# z-two.net
KiCad netlist of a schematic drawn in EAGLE
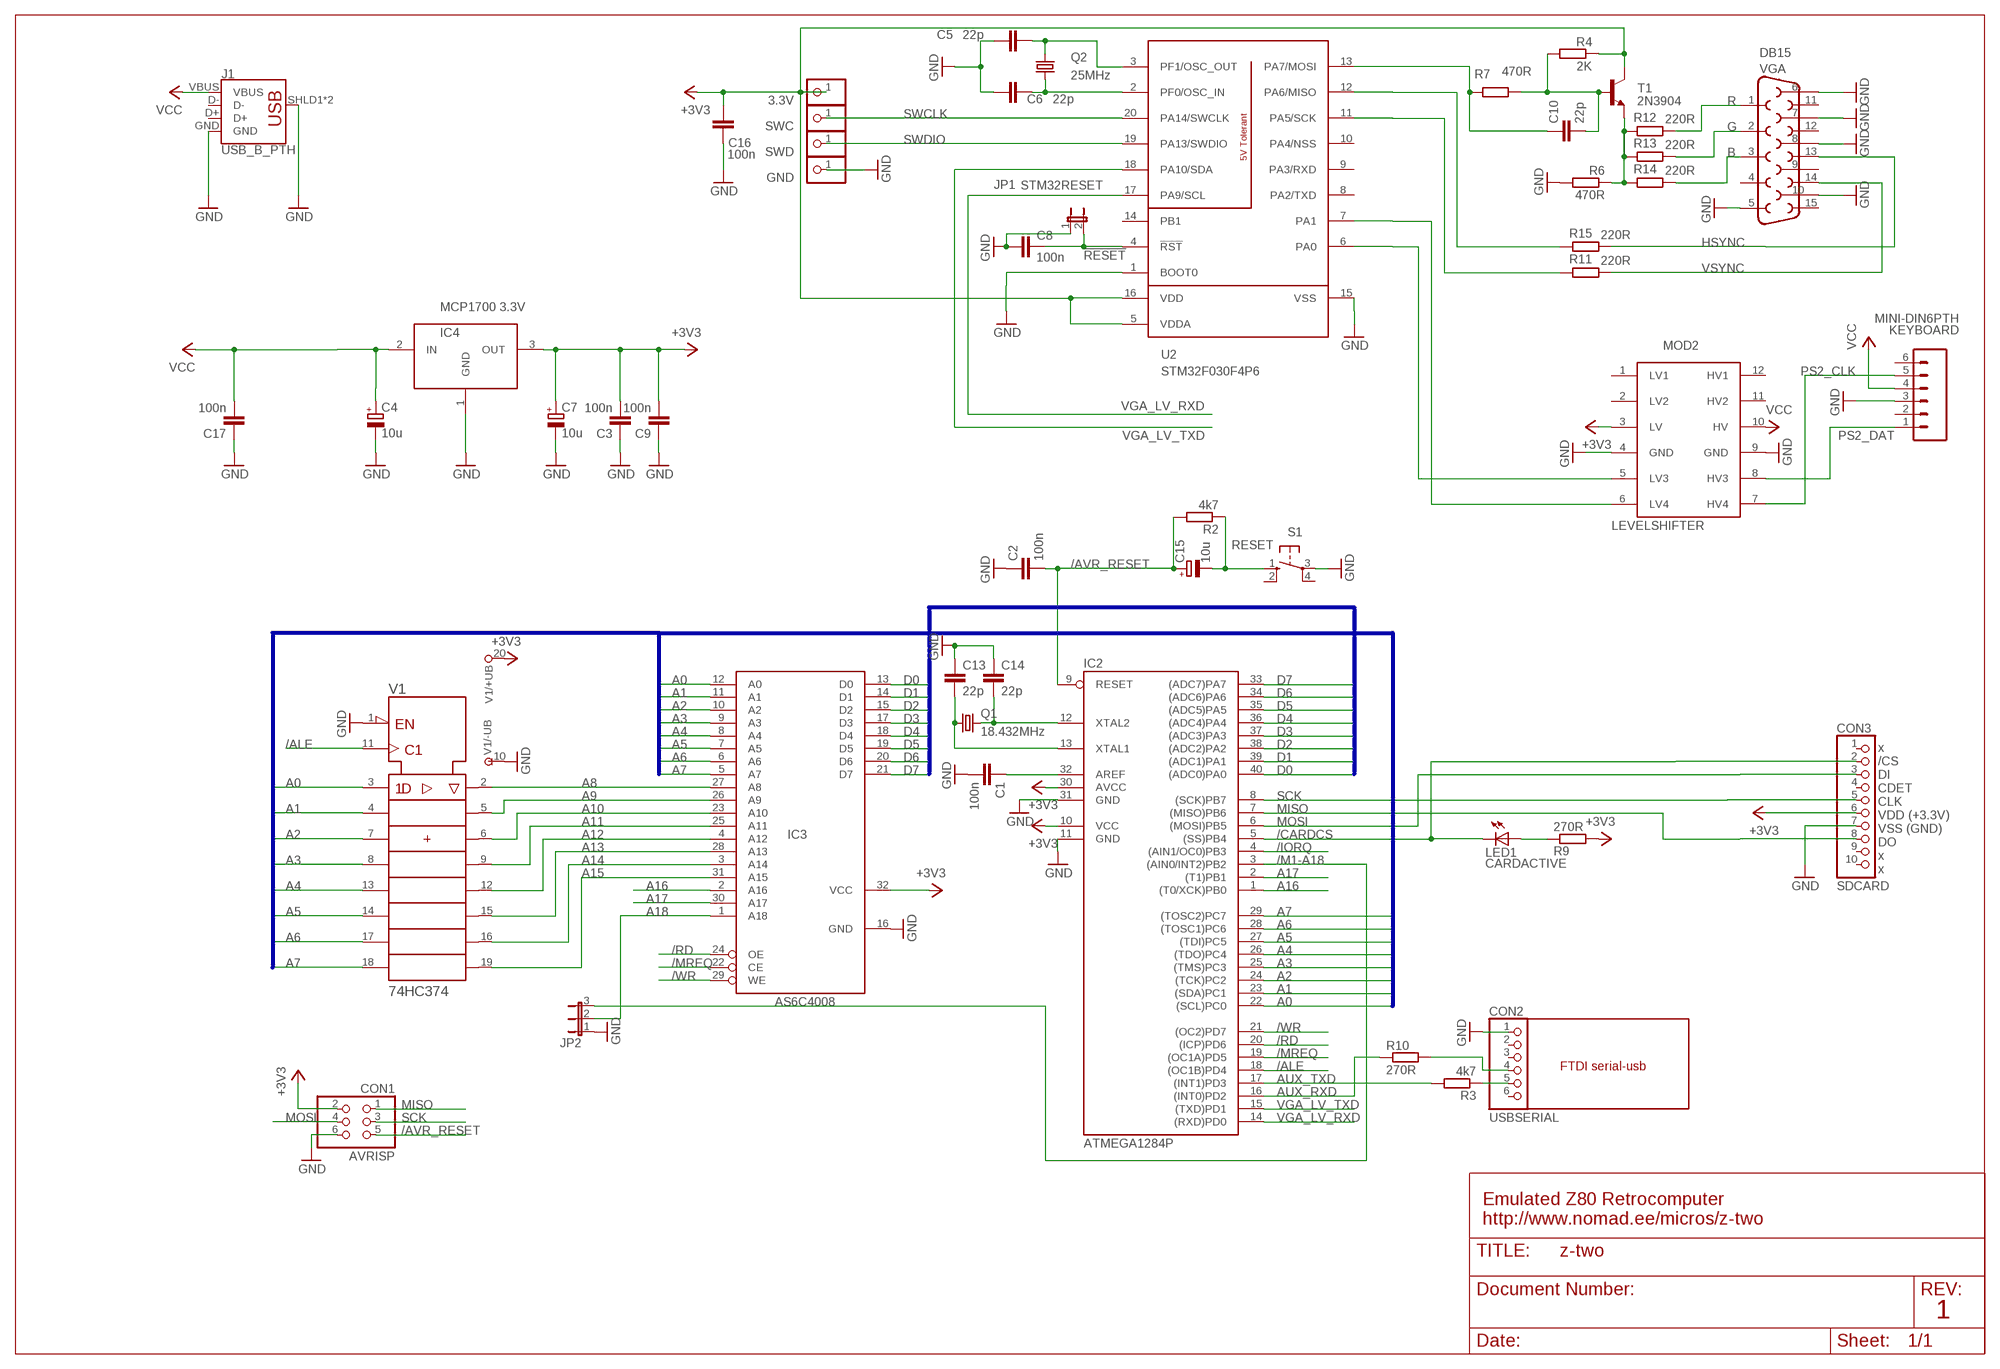
[diagram p0: schematic, sheet 1]

(export (version "E")
  (design (tool "Eeschema 10.0.6"))
  (components
    (comp (ref "3.3V")
      (value "PINHD-1X1")
      (footprint "eagle-import:1X01")
      (libsource (lib "eagle-import") (part "PINHD-1X1"))
    )
    (comp (ref "C1")
      (value "100n")
      (footprint "eagle-import:C025-025X050")
      (fields (field (name "PARTNO") "0.1UF, 0603"))
      (libsource (lib "eagle-import") (part "C-EU025-025X050"))
    )
    (comp (ref "C2")
      (value "100n")
      (footprint "eagle-import:C025-025X050")
      (fields (field (name "PARTNO") "0.1UF, 0603"))
      (libsource (lib "eagle-import") (part "C-EU025-025X050"))
    )
    (comp (ref "C3")
      (value "100n")
      (footprint "eagle-import:C025-025X050")
      (fields (field (name "PARTNO") "0.1UF, 0603"))
      (libsource (lib "eagle-import") (part "C-EU025-025X050"))
    )
    (comp (ref "C4")
      (value "10u")
      (footprint "eagle-import:E2,5-5")
      (libsource (lib "eagle-import") (part "CPOL-EUE2.5-5"))
    )
    (comp (ref "C5")
      (value "22p")
      (footprint "eagle-import:C025-025X050")
      (fields (field (name "PARTNO") "22PF, 0603"))
      (libsource (lib "eagle-import") (part "C-EU025-025X050"))
    )
    (comp (ref "C6")
      (value "22p")
      (footprint "eagle-import:C025-025X050")
      (fields (field (name "PARTNO") "22PF, 0603"))
      (libsource (lib "eagle-import") (part "C-EU025-025X050"))
    )
    (comp (ref "C7")
      (value "10u")
      (footprint "eagle-import:E2,5-5")
      (libsource (lib "eagle-import") (part "CPOL-EUE2.5-5"))
    )
    (comp (ref "C8")
      (value "100n")
      (footprint "eagle-import:C025-025X050")
      (fields (field (name "PARTNO") "0.1UF, 0603"))
      (libsource (lib "eagle-import") (part "C-EU025-025X050"))
    )
    (comp (ref "C9")
      (value "100n")
      (footprint "eagle-import:C025-025X050")
      (fields (field (name "PARTNO") "0.1UF, 0603"))
      (libsource (lib "eagle-import") (part "C-EU025-025X050"))
    )
    (comp (ref "C10")
      (value "22p")
      (footprint "eagle-import:C025-025X050")
      (fields (field (name "PARTNO") "22PF, 0603"))
      (libsource (lib "eagle-import") (part "C-EU025-025X050"))
    )
    (comp (ref "C13")
      (value "22p")
      (footprint "eagle-import:C025-025X050")
      (fields (field (name "PARTNO") "0.1UF, 0603"))
      (libsource (lib "eagle-import") (part "C-EU025-025X050"))
    )
    (comp (ref "C14")
      (value "22p")
      (footprint "eagle-import:C025-025X050")
      (fields (field (name "PARTNO") "0.1UF, 0603"))
      (libsource (lib "eagle-import") (part "C-EU025-025X050"))
    )
    (comp (ref "C15")
      (value "10u")
      (footprint "eagle-import:E2,5-5")
      (libsource (lib "eagle-import") (part "CPOL-EUE2.5-5"))
    )
    (comp (ref "C16")
      (value "100n")
      (footprint "eagle-import:C025-025X050")
      (fields (field (name "PARTNO") "0.1UF, 0603"))
      (libsource (lib "eagle-import") (part "C-EU025-025X050"))
    )
    (comp (ref "C17")
      (value "100n")
      (footprint "eagle-import:C025-025X050")
      (fields (field (name "PARTNO") "0.1UF, 0603"))
      (libsource (lib "eagle-import") (part "C-EU025-025X050"))
    )
    (comp (ref "CON1")
      (value "AVRISP")
      (footprint "eagle-import:2X03")
      (libsource (lib "eagle-import") (part "PINHD-2X3"))
    )
    (comp (ref "CON2")
      (value "USBSERIAL")
      (footprint "eagle-import:1X06")
      (libsource (lib "eagle-import") (part "PINHD-1X6"))
    )
    (comp (ref "CON3")
      (value "SDCARD")
      (footprint "eagle-import:1X10")
      (libsource (lib "eagle-import") (part "PINHD-1X10"))
    )
    (comp (ref "GND")
      (value "PINHD-1X1")
      (footprint "eagle-import:1X01")
      (libsource (lib "eagle-import") (part "PINHD-1X1"))
    )
    (comp (ref "IC2")
      (value "ATMEGA1284P")
      (footprint "eagle-import:DIL40")
      (fields (field (name "MPN") "ATMEGA32-16PU"))
      (libsource (lib "eagle-import") (part "MEGA32-P"))
    )
    (comp (ref "IC3")
      (value "AS6C4008")
      (footprint "eagle-import:DIP32")
      (libsource (lib "eagle-import") (part "AS6C4008DIP32"))
    )
    (comp (ref "IC4")
      (value "MCP1700 3.3V")
      (footprint "eagle-import:TO-92")
      (libsource (lib "eagle-import") (part "MCP1700TO92"))
    )
    (comp (ref "J1")
      (value "USB_B_PTH")
      (footprint "eagle-import:USB-B-PTH")
      (libsource (lib "eagle-import") (part "USB_B_PTH"))
    )
    (comp (ref "JP1")
      (value "STM32RESET")
      (footprint "eagle-import:1X02")
      (libsource (lib "eagle-import") (part "JUMPER-2PTH"))
    )
    (comp (ref "JP2")
      (value "JP2E")
      (footprint "eagle-import:JP2")
      (libsource (lib "eagle-import") (part "JP2E"))
    )
    (comp (ref "KEYBOARD")
      (value "MINI-DIN6PTH")
      (footprint "eagle-import:MINI-DIN6")
      (libsource (lib "eagle-import") (part "MINI-DIN6PTH"))
    )
    (comp (ref "LED1")
      (value "CARDACTIVE")
      (footprint "eagle-import:LED3MM")
      (libsource (lib "eagle-import") (part "LED3MM"))
    )
    (comp (ref "MOD2")
      (value "LEVELSHIFTER")
      (footprint "eagle-import:LAVELSHIFTER_N")
      (libsource (lib "eagle-import") (part "LEVELSHIFTERNARROW"))
    )
    (comp (ref "Q1")
      (value "18.432MHz")
      (footprint "eagle-import:HC49_S")
      (libsource (lib "eagle-import") (part "CRYSTALHC49S"))
    )
    (comp (ref "Q2")
      (value "25MHz")
      (footprint "eagle-import:HC49_S")
      (libsource (lib "eagle-import") (part "CRYSTALHC49S"))
    )
    (comp (ref "R2")
      (value "4k7")
      (footprint "eagle-import:0204_7")
      (libsource (lib "eagle-import") (part "R-EU_0204/7"))
    )
    (comp (ref "R3")
      (value "4k7")
      (footprint "eagle-import:0204_7")
      (libsource (lib "eagle-import") (part "R-EU_0204/7"))
    )
    (comp (ref "R4")
      (value "2K")
      (footprint "eagle-import:0204_7")
      (fields (field (name "PARTNO") "2K, 0603"))
      (libsource (lib "eagle-import") (part "resistor_R-EU_0204/7"))
    )
    (comp (ref "R6")
      (value "470R")
      (footprint "eagle-import:0204_7")
      (fields (field (name "PARTNO") "475R, 0603"))
      (libsource (lib "eagle-import") (part "resistor_R-EU_0204/7"))
    )
    (comp (ref "R7")
      (value "470R")
      (footprint "eagle-import:0204_7")
      (fields (field (name "PARTNO") "475R, 0603"))
      (libsource (lib "eagle-import") (part "resistor_R-EU_0204/7"))
    )
    (comp (ref "R9")
      (value "270R")
      (footprint "eagle-import:0204_7")
      (fields (field (name "PARTNO") "475R, 0603"))
      (libsource (lib "eagle-import") (part "resistor_R-EU_0204/7"))
    )
    (comp (ref "R10")
      (value "270R")
      (footprint "eagle-import:0204_7")
      (libsource (lib "eagle-import") (part "R-EU_0204/7"))
    )
    (comp (ref "R11")
      (value "220R")
      (footprint "eagle-import:0204_7")
      (libsource (lib "eagle-import") (part "resistor_R-EU_0204/7"))
    )
    (comp (ref "R12")
      (value "220R")
      (footprint "eagle-import:0204_7")
      (libsource (lib "eagle-import") (part "resistor_R-EU_0204/7"))
    )
    (comp (ref "R13")
      (value "220R")
      (footprint "eagle-import:0204_7")
      (libsource (lib "eagle-import") (part "resistor_R-EU_0204/7"))
    )
    (comp (ref "R14")
      (value "220R")
      (footprint "eagle-import:0204_7")
      (libsource (lib "eagle-import") (part "resistor_R-EU_0204/7"))
    )
    (comp (ref "R15")
      (value "220R")
      (footprint "eagle-import:0204_7")
      (libsource (lib "eagle-import") (part "resistor_R-EU_0204/7"))
    )
    (comp (ref "S1")
      (value "RESET")
      (footprint "eagle-import:B3F-10XX")
      (fields (field (name "MPN") "B3F-1000"))
      (libsource (lib "eagle-import") (part "10-XX"))
    )
    (comp (ref "SWC")
      (value "PINHD-1X1")
      (footprint "eagle-import:1X01")
      (libsource (lib "eagle-import") (part "PINHD-1X1"))
    )
    (comp (ref "SWD")
      (value "PINHD-1X1")
      (footprint "eagle-import:1X01")
      (libsource (lib "eagle-import") (part "PINHD-1X1"))
    )
    (comp (ref "T1")
      (value "2N3904")
      (footprint "eagle-import:TO92")
      (libsource (lib "eagle-import") (part "2N3904"))
    )
    (comp (ref "U2")
      (value "STM32F030F4P6")
      (footprint "eagle-import:MISC-PROCESSOR_TSSOP20")
      (libsource (lib "eagle-import") (part "MISC-PROCESSOR_STM32F030F4P6"))
    )
    (comp (ref "V1")
      (value "74HC374")
      (footprint "eagle-import:DIL20")
      (libsource (lib "eagle-import") (part "74374N"))
    )
    (comp (ref "VGA")
      (value "DB15")
      (footprint "eagle-import:DB15")
      (libsource (lib "eagle-import") (part "DB15"))
    )
  )
  (nets
    (net (code "1") (name "+3V3") (class "Default")
      (node (ref "3.3V") (pin "1") (pinfunction "1_1") (pintype "passive"))
      (node (ref "C16") (pin "1") (pinfunction "1_1") (pintype "passive"))
      (node (ref "C3") (pin "2") (pinfunction "2_2") (pintype "passive"))
      (node (ref "C7") (pin "+") (pinfunction "+_+") (pintype "passive"))
      (node (ref "C9") (pin "2") (pinfunction "2_2") (pintype "passive"))
      (node (ref "CON1") (pin "2") (pinfunction "2_2") (pintype "passive"))
      (node (ref "CON3") (pin "6") (pinfunction "6_6") (pintype "passive"))
      (node (ref "IC2") (pin "10") (pinfunction "VCC_10") (pintype "power_in"))
      (node (ref "IC2") (pin "30") (pinfunction "AVCC_30") (pintype "power_in"))
      (node (ref "IC3") (pin "32") (pinfunction "VCC_32") (pintype "power_in"))
      (node (ref "IC4") (pin "3") (pinfunction "OUT_3") (pintype "bidirectional"))
      (node (ref "MOD2") (pin "3") (pinfunction "LV_3") (pintype "bidirectional"))
      (node (ref "R4") (pin "1") (pinfunction "1_1") (pintype "passive"))
      (node (ref "R9") (pin "2") (pinfunction "2_2") (pintype "passive"))
      (node (ref "T1") (pin "1") (pinfunction "C_1") (pintype "passive"))
      (node (ref "U2") (pin "16") (pinfunction "VDD_16") (pintype "input"))
      (node (ref "U2") (pin "5") (pinfunction "VDDA_5") (pintype "input"))
      (node (ref "V1") (pin "20") (pinfunction "+UB_20") (pintype "power_in"))
    )
    (net (code "2") (name "/A0") (class "Default")
      (node (ref "IC2") (pin "22") (pinfunction "(SCL)PC0_22") (pintype "bidirectional"))
      (node (ref "IC3") (pin "12") (pinfunction "A0_12") (pintype "input"))
      (node (ref "V1") (pin "3") (pinfunction "1D_3") (pintype "input"))
    )
    (net (code "3") (name "/A1") (class "Default")
      (node (ref "IC2") (pin "23") (pinfunction "(SDA)PC1_23") (pintype "bidirectional"))
      (node (ref "IC3") (pin "11") (pinfunction "A1_11") (pintype "input"))
      (node (ref "V1") (pin "4") (pinfunction "2D_4") (pintype "input"))
    )
    (net (code "4") (name "/A2") (class "Default")
      (node (ref "IC2") (pin "24") (pinfunction "(TCK)PC2_24") (pintype "bidirectional"))
      (node (ref "IC3") (pin "10") (pinfunction "A2_10") (pintype "input"))
      (node (ref "V1") (pin "7") (pinfunction "3D_7") (pintype "input"))
    )
    (net (code "5") (name "/A3") (class "Default")
      (node (ref "IC2") (pin "25") (pinfunction "(TMS)PC3_25") (pintype "bidirectional"))
      (node (ref "IC3") (pin "9") (pinfunction "A3_9") (pintype "input"))
      (node (ref "V1") (pin "8") (pinfunction "4D_8") (pintype "input"))
    )
    (net (code "6") (name "/A4") (class "Default")
      (node (ref "IC2") (pin "26") (pinfunction "(TDO)PC4_26") (pintype "bidirectional"))
      (node (ref "IC3") (pin "8") (pinfunction "A4_8") (pintype "input"))
      (node (ref "V1") (pin "13") (pinfunction "5D_13") (pintype "input"))
    )
    (net (code "7") (name "/A5") (class "Default")
      (node (ref "IC2") (pin "27") (pinfunction "(TDI)PC5_27") (pintype "bidirectional"))
      (node (ref "IC3") (pin "7") (pinfunction "A5_7") (pintype "input"))
      (node (ref "V1") (pin "14") (pinfunction "6D_14") (pintype "input"))
    )
    (net (code "8") (name "/A6") (class "Default")
      (node (ref "IC2") (pin "28") (pinfunction "(TOSC1)PC6_28") (pintype "bidirectional"))
      (node (ref "IC3") (pin "6") (pinfunction "A6_6") (pintype "input"))
      (node (ref "V1") (pin "17") (pinfunction "7D_17") (pintype "input"))
    )
    (net (code "9") (name "/A7") (class "Default")
      (node (ref "IC2") (pin "29") (pinfunction "(TOSC2)PC7_29") (pintype "bidirectional"))
      (node (ref "IC3") (pin "5") (pinfunction "A7_5") (pintype "input"))
      (node (ref "V1") (pin "18") (pinfunction "8D_18") (pintype "input"))
    )
    (net (code "10") (name "/A8") (class "Default")
      (node (ref "IC3") (pin "27") (pinfunction "A8_27") (pintype "input"))
      (node (ref "V1") (pin "2") (pinfunction "1Q_2") (pintype "tri_state"))
    )
    (net (code "11") (name "/A9") (class "Default")
      (node (ref "IC3") (pin "26") (pinfunction "A9_26") (pintype "input"))
      (node (ref "V1") (pin "5") (pinfunction "2Q_5") (pintype "tri_state"))
    )
    (net (code "12") (name "/A10") (class "Default")
      (node (ref "IC3") (pin "23") (pinfunction "A10_23") (pintype "input"))
      (node (ref "V1") (pin "6") (pinfunction "3Q_6") (pintype "tri_state"))
    )
    (net (code "13") (name "/A11") (class "Default")
      (node (ref "IC3") (pin "25") (pinfunction "A11_25") (pintype "input"))
      (node (ref "V1") (pin "9") (pinfunction "4Q_9") (pintype "tri_state"))
    )
    (net (code "14") (name "/A12") (class "Default")
      (node (ref "IC3") (pin "4") (pinfunction "A12_4") (pintype "input"))
      (node (ref "V1") (pin "12") (pinfunction "5Q_12") (pintype "tri_state"))
    )
    (net (code "15") (name "/A13") (class "Default")
      (node (ref "IC3") (pin "28") (pinfunction "A13_28") (pintype "input"))
      (node (ref "V1") (pin "15") (pinfunction "6Q_15") (pintype "tri_state"))
    )
    (net (code "16") (name "/A14") (class "Default")
      (node (ref "IC3") (pin "3") (pinfunction "A14_3") (pintype "input"))
      (node (ref "V1") (pin "16") (pinfunction "7Q_16") (pintype "tri_state"))
    )
    (net (code "17") (name "/A15") (class "Default")
      (node (ref "IC3") (pin "31") (pinfunction "A15_31") (pintype "input"))
      (node (ref "V1") (pin "19") (pinfunction "8Q_19") (pintype "tri_state"))
    )
    (net (code "18") (name "/A16") (class "Default")
      (node (ref "IC2") (pin "1") (pinfunction "(T0/XCK)PB0_1") (pintype "bidirectional"))
      (node (ref "IC3") (pin "2") (pinfunction "A16_2") (pintype "input"))
    )
    (net (code "19") (name "/A17") (class "Default")
      (node (ref "IC2") (pin "2") (pinfunction "(T1)PB1_2") (pintype "bidirectional"))
      (node (ref "IC3") (pin "30") (pinfunction "A17_30") (pintype "input"))
    )
    (net (code "20") (name "/A18") (class "Default")
      (node (ref "IC3") (pin "1") (pinfunction "A18_1") (pintype "input"))
      (node (ref "JP2") (pin "2") (pinfunction "2_2") (pintype "passive"))
    )
    (net (code "21") (name "/AUX_RXD") (class "Default")
      (node (ref "IC2") (pin "16") (pinfunction "(INT0)PD2_16") (pintype "bidirectional"))
      (node (ref "R10") (pin "1") (pinfunction "1_1") (pintype "passive"))
    )
    (net (code "22") (name "/AUX_TXD") (class "Default")
      (node (ref "IC2") (pin "17") (pinfunction "(INT1)PD3_17") (pintype "bidirectional"))
      (node (ref "R3") (pin "2") (pinfunction "2_2") (pintype "passive"))
    )
    (net (code "23") (name "/B") (class "Default")
      (node (ref "R14") (pin "1") (pinfunction "1_1") (pintype "passive"))
      (node (ref "VGA") (pin "3") (pinfunction "3_3") (pintype "passive"))
    )
    (net (code "24") (name "/D0") (class "Default")
      (node (ref "IC2") (pin "40") (pinfunction "(ADC0)PA0_40") (pintype "bidirectional"))
      (node (ref "IC3") (pin "13") (pinfunction "D0_13") (pintype "bidirectional"))
    )
    (net (code "25") (name "/D1") (class "Default")
      (node (ref "IC2") (pin "39") (pinfunction "(ADC1)PA1_39") (pintype "bidirectional"))
      (node (ref "IC3") (pin "14") (pinfunction "D1_14") (pintype "bidirectional"))
    )
    (net (code "26") (name "/D2") (class "Default")
      (node (ref "IC2") (pin "38") (pinfunction "(ADC2)PA2_38") (pintype "bidirectional"))
      (node (ref "IC3") (pin "15") (pinfunction "D2_15") (pintype "bidirectional"))
    )
    (net (code "27") (name "/D3") (class "Default")
      (node (ref "IC2") (pin "37") (pinfunction "(ADC3)PA3_37") (pintype "bidirectional"))
      (node (ref "IC3") (pin "17") (pinfunction "D3_17") (pintype "bidirectional"))
    )
    (net (code "28") (name "/D4") (class "Default")
      (node (ref "IC2") (pin "36") (pinfunction "(ADC4)PA4_36") (pintype "bidirectional"))
      (node (ref "IC3") (pin "18") (pinfunction "D4_18") (pintype "bidirectional"))
    )
    (net (code "29") (name "/D5") (class "Default")
      (node (ref "IC2") (pin "35") (pinfunction "(ADC5)PA5_35") (pintype "bidirectional"))
      (node (ref "IC3") (pin "19") (pinfunction "D5_19") (pintype "bidirectional"))
    )
    (net (code "30") (name "/D6") (class "Default")
      (node (ref "IC2") (pin "34") (pinfunction "(ADC6)PA6_34") (pintype "bidirectional"))
      (node (ref "IC3") (pin "20") (pinfunction "D6_20") (pintype "bidirectional"))
    )
    (net (code "31") (name "/D7") (class "Default")
      (node (ref "IC2") (pin "33") (pinfunction "(ADC7)PA7_33") (pintype "bidirectional"))
      (node (ref "IC3") (pin "21") (pinfunction "D7_21") (pintype "bidirectional"))
    )
    (net (code "32") (name "/G") (class "Default")
      (node (ref "R13") (pin "1") (pinfunction "1_1") (pintype "passive"))
      (node (ref "VGA") (pin "2") (pinfunction "2_2") (pintype "passive"))
    )
    (net (code "33") (name "/HSYNC") (class "Default")
      (node (ref "R15") (pin "1") (pinfunction "1_1") (pintype "passive"))
      (node (ref "VGA") (pin "13") (pinfunction "13_13") (pintype "passive"))
    )
    (net (code "34") (name "/MISO") (class "Default")
      (node (ref "CON1") (pin "1") (pinfunction "1_1") (pintype "passive"))
      (node (ref "CON3") (pin "8") (pinfunction "8_8") (pintype "passive"))
      (node (ref "IC2") (pin "7") (pinfunction "(MISO)PB6_7") (pintype "bidirectional"))
    )
    (net (code "35") (name "/MOSI") (class "Default")
      (node (ref "CON1") (pin "4") (pinfunction "4_4") (pintype "passive"))
      (node (ref "CON3") (pin "3") (pinfunction "3_3") (pintype "passive"))
      (node (ref "IC2") (pin "6") (pinfunction "(MOSI)PB5_6") (pintype "bidirectional"))
    )
    (net (code "36") (name "/PS2_CLK") (class "Default")
      (node (ref "KEYBOARD") (pin "5") (pinfunction "5_5") (pintype "passive"))
      (node (ref "MOD2") (pin "7") (pinfunction "HV4_7") (pintype "bidirectional"))
    )
    (net (code "37") (name "/PS2_DAT") (class "Default")
      (node (ref "KEYBOARD") (pin "1") (pinfunction "1_1") (pintype "passive"))
      (node (ref "MOD2") (pin "8") (pinfunction "HV3_8") (pintype "bidirectional"))
    )
    (net (code "38") (name "/R") (class "Default")
      (node (ref "R12") (pin "1") (pinfunction "1_1") (pintype "passive"))
      (node (ref "VGA") (pin "1") (pinfunction "1_1") (pintype "passive"))
    )
    (net (code "39") (name "/SCK") (class "Default")
      (node (ref "CON1") (pin "3") (pinfunction "3_3") (pintype "passive"))
      (node (ref "CON3") (pin "5") (pinfunction "5_5") (pintype "passive"))
      (node (ref "IC2") (pin "8") (pinfunction "(SCK)PB7_8") (pintype "bidirectional"))
    )
    (net (code "40") (name "/SWCLK") (class "Default")
      (node (ref "SWC") (pin "1") (pinfunction "1_1") (pintype "passive"))
      (node (ref "U2") (pin "20") (pinfunction "PA14/SWCLK_20") (pintype "bidirectional"))
    )
    (net (code "41") (name "/SWDIO") (class "Default")
      (node (ref "SWD") (pin "1") (pinfunction "1_1") (pintype "passive"))
      (node (ref "U2") (pin "19") (pinfunction "PA13/SWDIO_19") (pintype "bidirectional"))
    )
    (net (code "42") (name "/VGA_LV_RXD") (class "Default")
      (node (ref "IC2") (pin "14") (pinfunction "(RXD)PD0_14") (pintype "bidirectional"))
      (node (ref "U2") (pin "17") (pinfunction "PA9/SCL_17") (pintype "bidirectional"))
    )
    (net (code "43") (name "/VGA_LV_TXD") (class "Default")
      (node (ref "IC2") (pin "15") (pinfunction "(TXD)PD1_15") (pintype "bidirectional"))
      (node (ref "U2") (pin "18") (pinfunction "PA10/SDA_18") (pintype "bidirectional"))
    )
    (net (code "44") (name "/VSYNC") (class "Default")
      (node (ref "R11") (pin "1") (pinfunction "1_1") (pintype "passive"))
      (node (ref "VGA") (pin "14") (pinfunction "14_14") (pintype "passive"))
    )
    (net (code "45") (name "/{slash}ALE") (class "Default")
      (node (ref "IC2") (pin "18") (pinfunction "(OC1B)PD4_18") (pintype "bidirectional"))
      (node (ref "V1") (pin "11") (pinfunction "CLK_11") (pintype "input"))
    )
    (net (code "46") (name "/{slash}AVR_RESET") (class "Default")
      (node (ref "C15") (pin "+") (pinfunction "+_+") (pintype "passive"))
      (node (ref "C2") (pin "2") (pinfunction "2_2") (pintype "passive"))
      (node (ref "CON1") (pin "5") (pinfunction "5_5") (pintype "passive"))
      (node (ref "IC2") (pin "9") (pinfunction "RESET_9") (pintype "input"))
      (node (ref "R2") (pin "2") (pinfunction "2_2") (pintype "passive"))
    )
    (net (code "47") (name "/{slash}CARDCS") (class "Default")
      (node (ref "CON3") (pin "2") (pinfunction "2_2") (pintype "passive"))
      (node (ref "IC2") (pin "5") (pinfunction "(SS)PB4_5") (pintype "bidirectional"))
      (node (ref "LED1") (pin "K") (pinfunction "C_K") (pintype "passive"))
    )
    (net (code "48") (name "/{slash}IORQ") (class "Default")
      (node (ref "IC2") (pin "4") (pinfunction "(AIN1/OC0)PB3_4") (pintype "bidirectional"))
    )
    (net (code "49") (name "/{slash}M1-A18") (class "Default")
      (node (ref "IC2") (pin "3") (pinfunction "(AIN0/INT2)PB2_3") (pintype "bidirectional"))
      (node (ref "JP2") (pin "3") (pinfunction "3_3") (pintype "passive"))
    )
    (net (code "50") (name "/{slash}MREQ") (class "Default")
      (node (ref "IC2") (pin "19") (pinfunction "(OC1A)PD5_19") (pintype "bidirectional"))
      (node (ref "IC3") (pin "22") (pinfunction "CE_22") (pintype "input"))
    )
    (net (code "51") (name "/{slash}RD") (class "Default")
      (node (ref "IC2") (pin "20") (pinfunction "(ICP)PD6_20") (pintype "bidirectional"))
      (node (ref "IC3") (pin "24") (pinfunction "OE_24") (pintype "input"))
    )
    (net (code "52") (name "/{slash}WR") (class "Default")
      (node (ref "IC2") (pin "21") (pinfunction "(OC2)PD7_21") (pintype "bidirectional"))
      (node (ref "IC3") (pin "29") (pinfunction "WE_29") (pintype "input"))
    )
    (net (code "53") (name "/~{RESET}") (class "Default")
      (node (ref "C8") (pin "1") (pinfunction "1_1") (pintype "passive"))
      (node (ref "JP1") (pin "2") (pinfunction "2_2") (pintype "passive"))
      (node (ref "U2") (pin "4") (pinfunction "~{RST}_4") (pintype "input"))
    )
    (net (code "54") (name "GND") (class "Default")
      (node (ref "C1") (pin "2") (pinfunction "2_2") (pintype "passive"))
      (node (ref "C13") (pin "1") (pinfunction "1_1") (pintype "passive"))
      (node (ref "C14") (pin "1") (pinfunction "1_1") (pintype "passive"))
      (node (ref "C16") (pin "2") (pinfunction "2_2") (pintype "passive"))
      (node (ref "C17") (pin "1") (pinfunction "1_1") (pintype "passive"))
      (node (ref "C2") (pin "1") (pinfunction "1_1") (pintype "passive"))
      (node (ref "C3") (pin "1") (pinfunction "1_1") (pintype "passive"))
      (node (ref "C4") (pin "-") (pinfunction "-_-") (pintype "passive"))
      (node (ref "C5") (pin "1") (pinfunction "1_1") (pintype "passive"))
      (node (ref "C6") (pin "1") (pinfunction "1_1") (pintype "passive"))
      (node (ref "C7") (pin "-") (pinfunction "-_-") (pintype "passive"))
      (node (ref "C8") (pin "2") (pinfunction "2_2") (pintype "passive"))
      (node (ref "C9") (pin "1") (pinfunction "1_1") (pintype "passive"))
      (node (ref "CON1") (pin "6") (pinfunction "6_6") (pintype "passive"))
      (node (ref "CON2") (pin "1") (pinfunction "1_1") (pintype "passive"))
      (node (ref "CON3") (pin "7") (pinfunction "7_7") (pintype "passive"))
      (node (ref "GND") (pin "1") (pinfunction "1_1") (pintype "passive"))
      (node (ref "IC2") (pin "11") (pinfunction "GND_11") (pintype "power_in"))
      (node (ref "IC2") (pin "31") (pinfunction "GND_31") (pintype "power_in"))
      (node (ref "IC3") (pin "16") (pinfunction "GND_16") (pintype "power_in"))
      (node (ref "IC4") (pin "1") (pinfunction "GND_1") (pintype "bidirectional"))
      (node (ref "J1") (pin "GND") (pinfunction "GND_GND") (pintype "power_in"))
      (node (ref "J1") (pin "SHLD1") (pinfunction "SHIELD_SHLD1") (pintype "bidirectional"))
      (node (ref "J1") (pin "SHLD2") (pinfunction "SHIELD_SHLD2") (pintype "bidirectional"))
      (node (ref "JP1") (pin "1") (pinfunction "1_1") (pintype "passive"))
      (node (ref "JP2") (pin "1") (pinfunction "1_1") (pintype "passive"))
      (node (ref "KEYBOARD") (pin "3") (pinfunction "3_3") (pintype "passive"))
      (node (ref "MOD2") (pin "4") (pinfunction "GND_4") (pintype "bidirectional"))
      (node (ref "MOD2") (pin "9") (pinfunction "GND_9") (pintype "bidirectional"))
      (node (ref "R6") (pin "2") (pinfunction "2_2") (pintype "passive"))
      (node (ref "S1") (pin "3") (pinfunction "P_3") (pintype "passive"))
      (node (ref "U2") (pin "1") (pinfunction "BOOT0_1") (pintype "input"))
      (node (ref "U2") (pin "15") (pinfunction "VSS_15") (pintype "input"))
      (node (ref "V1") (pin "1") (pinfunction "~{OC}_1") (pintype "input"))
      (node (ref "V1") (pin "10") (pinfunction "-UB_10") (pintype "power_in"))
      (node (ref "VGA") (pin "10") (pinfunction "10_10") (pintype "passive"))
      (node (ref "VGA") (pin "5") (pinfunction "5_5") (pintype "passive"))
      (node (ref "VGA") (pin "6") (pinfunction "6_6") (pintype "passive"))
      (node (ref "VGA") (pin "7") (pinfunction "7_7") (pintype "passive"))
      (node (ref "VGA") (pin "8") (pinfunction "8_8") (pintype "passive"))
    )
    (net (code "55") (name "Net-(CON2-Pad4)") (class "Default")
      (node (ref "CON2") (pin "4") (pinfunction "4_4") (pintype "passive"))
      (node (ref "R10") (pin "2") (pinfunction "2_2") (pintype "passive"))
    )
    (net (code "56") (name "Net-(CON2-Pad5)") (class "Default")
      (node (ref "CON2") (pin "5") (pinfunction "5_5") (pintype "passive"))
      (node (ref "R3") (pin "1") (pinfunction "1_1") (pintype "passive"))
    )
    (net (code "57") (name "Net-(IC2-AREF)") (class "Default")
      (node (ref "C1") (pin "1") (pinfunction "1_1") (pintype "passive"))
      (node (ref "IC2") (pin "32") (pinfunction "AREF_32") (pintype "passive"))
    )
    (net (code "58") (name "Net-(IC2-XTAL1)") (class "Default")
      (node (ref "C13") (pin "2") (pinfunction "2_2") (pintype "passive"))
      (node (ref "IC2") (pin "13") (pinfunction "XTAL1_13") (pintype "bidirectional"))
      (node (ref "Q1") (pin "1") (pinfunction "1_1") (pintype "passive"))
    )
    (net (code "59") (name "Net-(IC2-XTAL2)") (class "Default")
      (node (ref "C14") (pin "2") (pinfunction "2_2") (pintype "passive"))
      (node (ref "IC2") (pin "12") (pinfunction "XTAL2_12") (pintype "bidirectional"))
      (node (ref "Q1") (pin "2") (pinfunction "2_2") (pintype "passive"))
    )
    (net (code "60") (name "Net-(LED1-PadA)") (class "Default")
      (node (ref "LED1") (pin "A") (pinfunction "A_A") (pintype "passive"))
      (node (ref "R9") (pin "1") (pinfunction "1_1") (pintype "passive"))
    )
    (net (code "61") (name "Net-(MOD2-LV3)") (class "Default")
      (node (ref "MOD2") (pin "5") (pinfunction "LV3_5") (pintype "bidirectional"))
      (node (ref "U2") (pin "6") (pinfunction "PA0_6") (pintype "bidirectional"))
    )
    (net (code "62") (name "Net-(MOD2-LV4)") (class "Default")
      (node (ref "MOD2") (pin "6") (pinfunction "LV4_6") (pintype "bidirectional"))
      (node (ref "U2") (pin "7") (pinfunction "PA1_7") (pintype "bidirectional"))
    )
    (net (code "63") (name "Net-(S1-S)") (class "Default")
      (node (ref "C15") (pin "-") (pinfunction "-_-") (pintype "passive"))
      (node (ref "R2") (pin "1") (pinfunction "1_1") (pintype "passive"))
      (node (ref "S1") (pin "1") (pinfunction "S_1") (pintype "passive"))
    )
    (net (code "64") (name "Net-(T1-B)") (class "Default")
      (node (ref "C10") (pin "2") (pinfunction "2_2") (pintype "passive"))
      (node (ref "R4") (pin "2") (pinfunction "2_2") (pintype "passive"))
      (node (ref "R7") (pin "1") (pinfunction "1_1") (pintype "passive"))
      (node (ref "T1") (pin "2") (pinfunction "B_2") (pintype "passive"))
    )
    (net (code "65") (name "Net-(T1-E)") (class "Default")
      (node (ref "R12") (pin "2") (pinfunction "2_2") (pintype "passive"))
      (node (ref "R13") (pin "2") (pinfunction "2_2") (pintype "passive"))
      (node (ref "R14") (pin "2") (pinfunction "2_2") (pintype "passive"))
      (node (ref "R6") (pin "1") (pinfunction "1_1") (pintype "passive"))
      (node (ref "T1") (pin "3") (pinfunction "E_3") (pintype "passive"))
    )
    (net (code "66") (name "Net-(U2-PA5{slash}SCK)") (class "Default")
      (node (ref "R11") (pin "2") (pinfunction "2_2") (pintype "passive"))
      (node (ref "U2") (pin "11") (pinfunction "PA5/SCK_11") (pintype "bidirectional"))
    )
    (net (code "67") (name "Net-(U2-PA6{slash}MISO)") (class "Default")
      (node (ref "R15") (pin "2") (pinfunction "2_2") (pintype "passive"))
      (node (ref "U2") (pin "12") (pinfunction "PA6/MISO_12") (pintype "bidirectional"))
    )
    (net (code "68") (name "Net-(U2-PA7{slash}MOSI)") (class "Default")
      (node (ref "C10") (pin "1") (pinfunction "1_1") (pintype "passive"))
      (node (ref "R7") (pin "2") (pinfunction "2_2") (pintype "passive"))
      (node (ref "U2") (pin "13") (pinfunction "PA7/MOSI_13") (pintype "bidirectional"))
    )
    (net (code "69") (name "Net-(U2-PF0{slash}OSC_IN)") (class "Default")
      (node (ref "C6") (pin "2") (pinfunction "2_2") (pintype "passive"))
      (node (ref "Q2") (pin "1") (pinfunction "1_1") (pintype "passive"))
      (node (ref "U2") (pin "2") (pinfunction "PF0/OSC_IN_2") (pintype "input"))
    )
    (net (code "70") (name "Net-(U2-PF1{slash}OSC_OUT)") (class "Default")
      (node (ref "C5") (pin "2") (pinfunction "2_2") (pintype "passive"))
      (node (ref "Q2") (pin "2") (pinfunction "2_2") (pintype "passive"))
      (node (ref "U2") (pin "3") (pinfunction "PF1/OSC_OUT_3") (pintype "output"))
    )
    (net (code "71") (name "VCC") (class "Default")
      (node (ref "C17") (pin "2") (pinfunction "2_2") (pintype "passive"))
      (node (ref "C4") (pin "+") (pinfunction "+_+") (pintype "passive"))
      (node (ref "IC4") (pin "2") (pinfunction "IN_2") (pintype "bidirectional"))
      (node (ref "J1") (pin "VBUS") (pinfunction "VBUS_VBUS") (pintype "power_in"))
      (node (ref "KEYBOARD") (pin "4") (pinfunction "4_4") (pintype "passive"))
      (node (ref "MOD2") (pin "10") (pinfunction "HV_10") (pintype "bidirectional"))
    )
    (net (code "72") (name "unconnected-(CON2-Pad2)") (class "Default")
      (node (ref "CON2") (pin "2") (pinfunction "2_2") (pintype "passive"))
    )
    (net (code "73") (name "unconnected-(CON2-Pad3)") (class "Default")
      (node (ref "CON2") (pin "3") (pinfunction "3_3") (pintype "passive"))
    )
    (net (code "74") (name "unconnected-(CON2-Pad6)") (class "Default")
      (node (ref "CON2") (pin "6") (pinfunction "6_6") (pintype "passive"))
    )
    (net (code "75") (name "unconnected-(CON3-Pad1)") (class "Default")
      (node (ref "CON3") (pin "1") (pinfunction "1_1") (pintype "passive"))
    )
    (net (code "76") (name "unconnected-(CON3-Pad4)") (class "Default")
      (node (ref "CON3") (pin "4") (pinfunction "4_4") (pintype "passive"))
    )
    (net (code "77") (name "unconnected-(CON3-Pad9)") (class "Default")
      (node (ref "CON3") (pin "9") (pinfunction "9_9") (pintype "passive"))
    )
    (net (code "78") (name "unconnected-(CON3-Pad10)") (class "Default")
      (node (ref "CON3") (pin "10") (pinfunction "10_10") (pintype "passive"))
    )
    (net (code "79") (name "unconnected-(J1-PadD+)") (class "Default")
      (node (ref "J1") (pin "D+") (pinfunction "D+_D+") (pintype "bidirectional"))
    )
    (net (code "80") (name "unconnected-(J1-PadD-)") (class "Default")
      (node (ref "J1") (pin "D-") (pinfunction "D-_D-") (pintype "bidirectional"))
    )
    (net (code "81") (name "unconnected-(KEYBOARD-Pad2)") (class "Default")
      (node (ref "KEYBOARD") (pin "2") (pinfunction "2_2") (pintype "passive"))
    )
    (net (code "82") (name "unconnected-(KEYBOARD-Pad6)") (class "Default")
      (node (ref "KEYBOARD") (pin "6") (pinfunction "6_6") (pintype "passive"))
    )
    (net (code "83") (name "unconnected-(MOD2-HV1-Pad12)") (class "Default")
      (node (ref "MOD2") (pin "12") (pinfunction "HV1_12") (pintype "bidirectional"))
    )
    (net (code "84") (name "unconnected-(MOD2-HV2-Pad11)") (class "Default")
      (node (ref "MOD2") (pin "11") (pinfunction "HV2_11") (pintype "bidirectional"))
    )
    (net (code "85") (name "unconnected-(MOD2-LV1-Pad1)") (class "Default")
      (node (ref "MOD2") (pin "1") (pinfunction "LV1_1") (pintype "bidirectional"))
    )
    (net (code "86") (name "unconnected-(MOD2-LV2-Pad2)") (class "Default")
      (node (ref "MOD2") (pin "2") (pinfunction "LV2_2") (pintype "bidirectional"))
    )
    (net (code "87") (name "unconnected-(S1-P1-Pad4)") (class "Default")
      (node (ref "S1") (pin "4") (pinfunction "P1_4") (pintype "passive"))
    )
    (net (code "88") (name "unconnected-(S1-S1-Pad2)") (class "Default")
      (node (ref "S1") (pin "2") (pinfunction "S1_2") (pintype "passive"))
    )
    (net (code "89") (name "unconnected-(U2-PA2{slash}TXD-Pad8)") (class "Default")
      (node (ref "U2") (pin "8") (pinfunction "PA2/TXD_8") (pintype "bidirectional"))
    )
    (net (code "90") (name "unconnected-(U2-PA3{slash}RXD-Pad9)") (class "Default")
      (node (ref "U2") (pin "9") (pinfunction "PA3/RXD_9") (pintype "bidirectional"))
    )
    (net (code "91") (name "unconnected-(U2-PA4{slash}NSS-Pad10)") (class "Default")
      (node (ref "U2") (pin "10") (pinfunction "PA4/NSS_10") (pintype "bidirectional"))
    )
    (net (code "92") (name "unconnected-(U2-PB1-Pad14)") (class "Default")
      (node (ref "U2") (pin "14") (pinfunction "PB1_14") (pintype "bidirectional"))
    )
    (net (code "93") (name "unconnected-(VGA-Pad4)") (class "Default")
      (node (ref "VGA") (pin "4") (pinfunction "4_4") (pintype "passive"))
    )
    (net (code "94") (name "unconnected-(VGA-Pad9)") (class "Default")
      (node (ref "VGA") (pin "9") (pinfunction "9_9") (pintype "passive"))
    )
    (net (code "95") (name "unconnected-(VGA-Pad11)") (class "Default")
      (node (ref "VGA") (pin "11") (pinfunction "11_11") (pintype "passive"))
    )
    (net (code "96") (name "unconnected-(VGA-Pad12)") (class "Default")
      (node (ref "VGA") (pin "12") (pinfunction "12_12") (pintype "passive"))
    )
    (net (code "97") (name "unconnected-(VGA-Pad15)") (class "Default")
      (node (ref "VGA") (pin "15") (pinfunction "15_15") (pintype "passive"))
    )
  )
)
